# untitled_AS_AVT.net
KiCad netlist of a schematic drawn in EAGLE
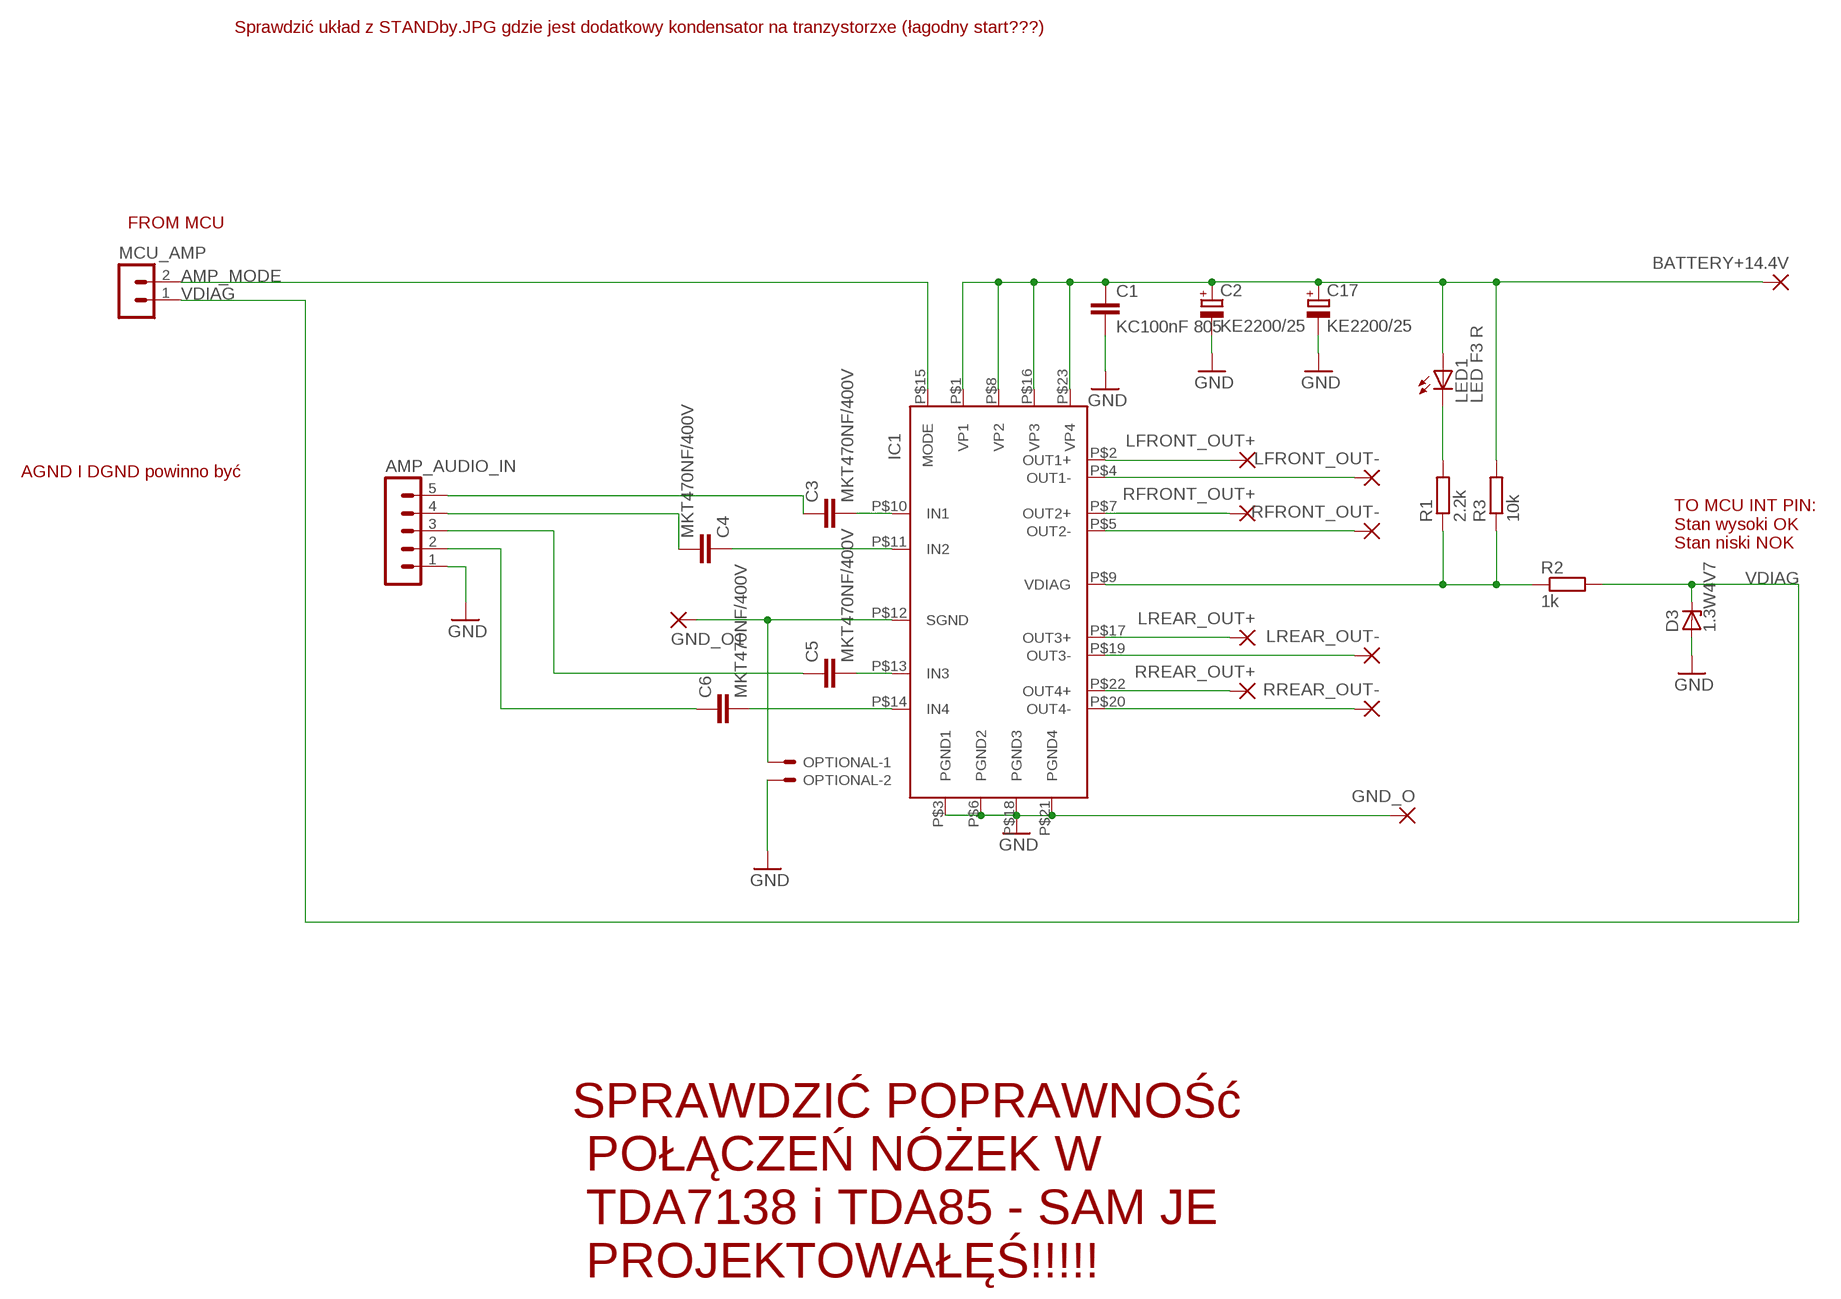
[diagram p0: schematic, sheet 1]

(export (version "E")
  (design (tool "Eeschema 10.0.6"))
  (components
    (comp (ref "AMP_AUDIO_IN")
      (value "MA05-1")
      (footprint "eagle-import:MA05-1")
      (fields (field (name "OC_FARNELL") "unknown") (field (name "OC_NEWARK") "unknown"))
      (libsource (lib "eagle-import") (part "MA05-1"))
    )
    (comp (ref "BATTERY+14.4V")
      (value "WIREPAD2,54/1,0")
      (footprint "eagle-import:2,54_1,0")
      (libsource (lib "eagle-import") (part "WIREPAD2,54/1,0"))
    )
    (comp (ref "C1")
      (value "KC100nF 805")
      (footprint "eagle-import:C0805")
      (libsource (lib "eagle-import") (part "C-EUC0805"))
    )
    (comp (ref "C2")
      (value "KE2200/25")
      (footprint "eagle-import:EB20D")
      (libsource (lib "eagle-import") (part "CPOL-EUE10-20"))
    )
    (comp (ref "C3")
      (value "MKT470NF/400V")
      (footprint "eagle-import:C025-024X044")
      (libsource (lib "eagle-import") (part "C-EU025-024X044"))
    )
    (comp (ref "C4")
      (value "MKT470NF/400V")
      (footprint "eagle-import:C025-024X044")
      (libsource (lib "eagle-import") (part "C-EU025-024X044"))
    )
    (comp (ref "C5")
      (value "MKT470NF/400V")
      (footprint "eagle-import:C025-024X044")
      (libsource (lib "eagle-import") (part "C-EU025-024X044"))
    )
    (comp (ref "C6")
      (value "MKT470NF/400V")
      (footprint "eagle-import:C025-024X044")
      (libsource (lib "eagle-import") (part "C-EU025-024X044"))
    )
    (comp (ref "C17")
      (value "KE2200/25")
      (footprint "eagle-import:EB20D")
      (libsource (lib "eagle-import") (part "CPOL-EUE10-20"))
    )
    (comp (ref "D3")
      (value "1.3W4V7")
      (footprint "eagle-import:ZDIO-5")
      (libsource (lib "eagle-import") (part "ZENER-DIODEZD-5"))
    )
    (comp (ref "GND_O")
      (value "WIREPAD2,54/1,0")
      (footprint "eagle-import:2,54_1,0")
      (libsource (lib "eagle-import") (part "WIREPAD2,54/1,0"))
    )
    (comp (ref "GND_O1")
      (value "WIREPAD2,54/1,0")
      (footprint "eagle-import:2,54_1,0")
      (libsource (lib "eagle-import") (part "WIREPAD2,54/1,0"))
    )
    (comp (ref "IC1")
      (value "TDA8571J")
      (footprint "eagle-import:SOT411-1")
      (libsource (lib "eagle-import") (part "TDA8571J"))
    )
    (comp (ref "LED1")
      (value "LED F3 R")
      (footprint "eagle-import:LED3MM")
      (libsource (lib "eagle-import") (part "LED3MM"))
    )
    (comp (ref "LFRONT_OUT+")
      (value "WIREPAD2,54/1,0")
      (footprint "eagle-import:2,54_1,0")
      (libsource (lib "eagle-import") (part "WIREPAD2,54/1,0"))
    )
    (comp (ref "LFRONT_OUT-")
      (value "WIREPAD2,54/1,0")
      (footprint "eagle-import:2,54_1,0")
      (libsource (lib "eagle-import") (part "WIREPAD2,54/1,0"))
    )
    (comp (ref "LREAR_OUT+")
      (value "WIREPAD2,54/1,0")
      (footprint "eagle-import:2,54_1,0")
      (libsource (lib "eagle-import") (part "WIREPAD2,54/1,0"))
    )
    (comp (ref "LREAR_OUT-")
      (value "WIREPAD2,54/1,0")
      (footprint "eagle-import:2,54_1,0")
      (libsource (lib "eagle-import") (part "WIREPAD2,54/1,0"))
    )
    (comp (ref "MCU_AMP")
      (value "MA02-1")
      (footprint "eagle-import:MA02-1")
      (libsource (lib "eagle-import") (part "MA02-1"))
    )
    (comp (ref "OPTIONAL")
      (value "332-02")
      (footprint "eagle-import:332-02")
      (libsource (lib "eagle-import") (part "332-02"))
    )
    (comp (ref "R1")
      (value "2.2k")
      (footprint "eagle-import:0204_5")
      (libsource (lib "eagle-import") (part "R-EU_0204/5"))
    )
    (comp (ref "R2")
      (value "1k")
      (footprint "eagle-import:0204_5")
      (libsource (lib "eagle-import") (part "R-EU_0204/5"))
    )
    (comp (ref "R3")
      (value "10k")
      (footprint "eagle-import:0204_5")
      (libsource (lib "eagle-import") (part "R-EU_0204/5"))
    )
    (comp (ref "RFRONT_OUT+")
      (value "WIREPAD2,54/1,0")
      (footprint "eagle-import:2,54_1,0")
      (libsource (lib "eagle-import") (part "WIREPAD2,54/1,0"))
    )
    (comp (ref "RFRONT_OUT-")
      (value "WIREPAD2,54/1,0")
      (footprint "eagle-import:2,54_1,0")
      (libsource (lib "eagle-import") (part "WIREPAD2,54/1,0"))
    )
    (comp (ref "RREAR_OUT+")
      (value "WIREPAD2,54/1,0")
      (footprint "eagle-import:2,54_1,0")
      (libsource (lib "eagle-import") (part "WIREPAD2,54/1,0"))
    )
    (comp (ref "RREAR_OUT-")
      (value "WIREPAD2,54/1,0")
      (footprint "eagle-import:2,54_1,0")
      (libsource (lib "eagle-import") (part "WIREPAD2,54/1,0"))
    )
  )
  (nets
    (net (code "1") (name "/AMP_MODE") (class "Default")
      (node (ref "IC1") (pin "P$15") (pinfunction "MODE_P$15") (pintype "bidirectional"))
      (node (ref "MCU_AMP") (pin "2") (pinfunction "2_2") (pintype "passive"))
    )
    (net (code "2") (name "/VDIAG") (class "Default")
      (node (ref "D3") (pin "C") (pinfunction "C_C") (pintype "passive"))
      (node (ref "MCU_AMP") (pin "1") (pinfunction "1_1") (pintype "passive"))
      (node (ref "R2") (pin "2") (pinfunction "2_2") (pintype "passive"))
    )
    (net (code "3") (name "GND") (class "Default")
      (node (ref "AMP_AUDIO_IN") (pin "1") (pinfunction "1_1") (pintype "passive"))
      (node (ref "C1") (pin "2") (pinfunction "2_2") (pintype "passive"))
      (node (ref "C17") (pin "-") (pinfunction "-_-") (pintype "passive"))
      (node (ref "C2") (pin "-") (pinfunction "-_-") (pintype "passive"))
      (node (ref "D3") (pin "A") (pinfunction "A_A") (pintype "passive"))
      (node (ref "GND_O") (pin "1") (pinfunction "P_1") (pintype "passive"))
      (node (ref "IC1") (pin "P$18") (pinfunction "PGND3_P$18") (pintype "power_in"))
      (node (ref "IC1") (pin "P$21") (pinfunction "PGND4_P$21") (pintype "power_in"))
      (node (ref "IC1") (pin "P$3") (pinfunction "PGND1_P$3") (pintype "power_in"))
      (node (ref "IC1") (pin "P$6") (pinfunction "PGND2_P$6") (pintype "power_in"))
      (node (ref "OPTIONAL") (pin "2") (pinfunction "S_2") (pintype "passive"))
    )
    (net (code "4") (name "Net-(AMP_AUDIO_IN-Pad2)") (class "Default")
      (node (ref "AMP_AUDIO_IN") (pin "2") (pinfunction "2_2") (pintype "passive"))
      (node (ref "C6") (pin "1") (pinfunction "1_1") (pintype "passive"))
    )
    (net (code "5") (name "Net-(AMP_AUDIO_IN-Pad3)") (class "Default")
      (node (ref "AMP_AUDIO_IN") (pin "3") (pinfunction "3_3") (pintype "passive"))
      (node (ref "C5") (pin "1") (pinfunction "1_1") (pintype "passive"))
    )
    (net (code "6") (name "Net-(AMP_AUDIO_IN-Pad4)") (class "Default")
      (node (ref "AMP_AUDIO_IN") (pin "4") (pinfunction "4_4") (pintype "passive"))
      (node (ref "C4") (pin "2") (pinfunction "2_2") (pintype "passive"))
    )
    (net (code "7") (name "Net-(AMP_AUDIO_IN-Pad5)") (class "Default")
      (node (ref "AMP_AUDIO_IN") (pin "5") (pinfunction "5_5") (pintype "passive"))
      (node (ref "C3") (pin "1") (pinfunction "1_1") (pintype "passive"))
    )
    (net (code "8") (name "Net-(BATTERY+14.4V-P)") (class "Default")
      (node (ref "BATTERY+14.4V") (pin "1") (pinfunction "P_1") (pintype "passive"))
      (node (ref "C1") (pin "1") (pinfunction "1_1") (pintype "passive"))
      (node (ref "C17") (pin "+") (pinfunction "+_+") (pintype "passive"))
      (node (ref "C2") (pin "+") (pinfunction "+_+") (pintype "passive"))
      (node (ref "IC1") (pin "P$1") (pinfunction "VP1_P$1") (pintype "power_in"))
      (node (ref "IC1") (pin "P$16") (pinfunction "VP3_P$16") (pintype "power_in"))
      (node (ref "IC1") (pin "P$23") (pinfunction "VP4_P$23") (pintype "power_in"))
      (node (ref "IC1") (pin "P$8") (pinfunction "VP2_P$8") (pintype "power_in"))
      (node (ref "LED1") (pin "A") (pinfunction "A_A") (pintype "passive"))
      (node (ref "R3") (pin "2") (pinfunction "2_2") (pintype "passive"))
    )
    (net (code "9") (name "Net-(GND_O1-P)") (class "Default")
      (node (ref "GND_O1") (pin "1") (pinfunction "P_1") (pintype "passive"))
      (node (ref "IC1") (pin "P$12") (pinfunction "SGND_P$12") (pintype "power_in"))
      (node (ref "OPTIONAL") (pin "1") (pinfunction "S_1") (pintype "passive"))
    )
    (net (code "10") (name "Net-(IC1-IN1)") (class "Default")
      (node (ref "C3") (pin "2") (pinfunction "2_2") (pintype "passive"))
      (node (ref "IC1") (pin "P$10") (pinfunction "IN1_P$10") (pintype "input"))
    )
    (net (code "11") (name "Net-(IC1-IN2)") (class "Default")
      (node (ref "C4") (pin "1") (pinfunction "1_1") (pintype "passive"))
      (node (ref "IC1") (pin "P$11") (pinfunction "IN2_P$11") (pintype "input"))
    )
    (net (code "12") (name "Net-(IC1-IN3)") (class "Default")
      (node (ref "C5") (pin "2") (pinfunction "2_2") (pintype "passive"))
      (node (ref "IC1") (pin "P$13") (pinfunction "IN3_P$13") (pintype "input"))
    )
    (net (code "13") (name "Net-(IC1-IN4)") (class "Default")
      (node (ref "C6") (pin "2") (pinfunction "2_2") (pintype "passive"))
      (node (ref "IC1") (pin "P$14") (pinfunction "IN4_P$14") (pintype "input"))
    )
    (net (code "14") (name "Net-(IC1-OUT1+)") (class "Default")
      (node (ref "IC1") (pin "P$2") (pinfunction "OUT1+_P$2") (pintype "output"))
      (node (ref "LFRONT_OUT+") (pin "1") (pinfunction "P_1") (pintype "passive"))
    )
    (net (code "15") (name "Net-(IC1-OUT1-)") (class "Default")
      (node (ref "IC1") (pin "P$4") (pinfunction "OUT1-_P$4") (pintype "output"))
      (node (ref "LFRONT_OUT-") (pin "1") (pinfunction "P_1") (pintype "passive"))
    )
    (net (code "16") (name "Net-(IC1-OUT2+)") (class "Default")
      (node (ref "IC1") (pin "P$7") (pinfunction "OUT2+_P$7") (pintype "output"))
      (node (ref "RFRONT_OUT+") (pin "1") (pinfunction "P_1") (pintype "passive"))
    )
    (net (code "17") (name "Net-(IC1-OUT2-)") (class "Default")
      (node (ref "IC1") (pin "P$5") (pinfunction "OUT2-_P$5") (pintype "output"))
      (node (ref "RFRONT_OUT-") (pin "1") (pinfunction "P_1") (pintype "passive"))
    )
    (net (code "18") (name "Net-(IC1-OUT3+)") (class "Default")
      (node (ref "IC1") (pin "P$17") (pinfunction "OUT3+_P$17") (pintype "output"))
      (node (ref "LREAR_OUT+") (pin "1") (pinfunction "P_1") (pintype "passive"))
    )
    (net (code "19") (name "Net-(IC1-OUT3-)") (class "Default")
      (node (ref "IC1") (pin "P$19") (pinfunction "OUT3-_P$19") (pintype "output"))
      (node (ref "LREAR_OUT-") (pin "1") (pinfunction "P_1") (pintype "passive"))
    )
    (net (code "20") (name "Net-(IC1-OUT4+)") (class "Default")
      (node (ref "IC1") (pin "P$22") (pinfunction "OUT4+_P$22") (pintype "output"))
      (node (ref "RREAR_OUT+") (pin "1") (pinfunction "P_1") (pintype "passive"))
    )
    (net (code "21") (name "Net-(IC1-OUT4-)") (class "Default")
      (node (ref "IC1") (pin "P$20") (pinfunction "OUT4-_P$20") (pintype "output"))
      (node (ref "RREAR_OUT-") (pin "1") (pinfunction "P_1") (pintype "passive"))
    )
    (net (code "22") (name "Net-(IC1-VDIAG)") (class "Default")
      (node (ref "IC1") (pin "P$9") (pinfunction "VDIAG_P$9") (pintype "bidirectional"))
      (node (ref "R1") (pin "1") (pinfunction "1_1") (pintype "passive"))
      (node (ref "R2") (pin "1") (pinfunction "1_1") (pintype "passive"))
      (node (ref "R3") (pin "1") (pinfunction "1_1") (pintype "passive"))
    )
    (net (code "23") (name "Net-(LED1-C)") (class "Default")
      (node (ref "LED1") (pin "K") (pinfunction "C_K") (pintype "passive"))
      (node (ref "R1") (pin "2") (pinfunction "2_2") (pintype "passive"))
    )
  )
)
